# 2_power.net
KiCad netlist of a schematic drawn in Altium Designer
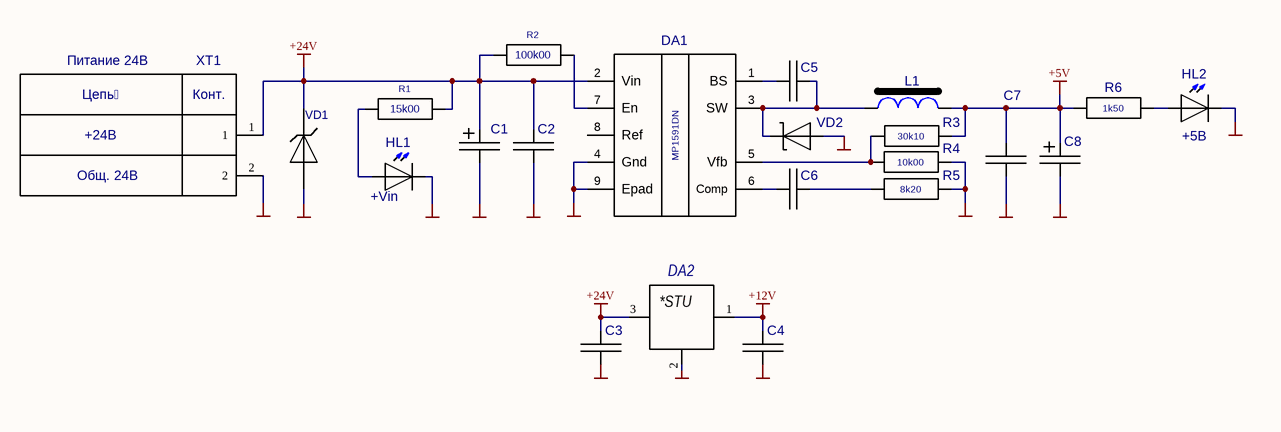
[diagram p0: 2 power.SchDoc]

(export (version "E")
  (design (tool "Eeschema 10.0.6"))
  (components
    (comp (ref "C1")
      (value "22.0x35V")
      (footprint "конденсаторы:TC7343-D")
      (description "TC6032-D")
      (libsource (lib "*") (part "TC6032-D"))
    )
    (comp (ref "C2") (value "C0603") (footprint "конденсаторы:0603_CAP") (libsource (lib "*") (part "C0603")))
    (comp (ref "C3") (value "C0603") (footprint "конденсаторы:0603_CAP") (libsource (lib "*") (part "C0603")))
    (comp (ref "C4") (value "C0603") (footprint "конденсаторы:0603_CAP") (libsource (lib "*") (part "C0603")))
    (comp (ref "C5") (value "C0603") (footprint "конденсаторы:0603_CAP") (libsource (lib "*") (part "C0603")))
    (comp (ref "C6") (value "C0603") (footprint "конденсаторы:0603_CAP") (libsource (lib "*") (part "C0603")))
    (comp (ref "C7") (value "C0603") (footprint "конденсаторы:0603_CAP") (libsource (lib "*") (part "C0603")))
    (comp (ref "C8")
      (value "100.0x16V")
      (footprint "конденсаторы:TC7343-D")
      (description "TC7343-D")
      (libsource (lib "конденсаторы") (part "TC7343-D"))
    )
    (comp (ref "DA1") (value "MP1591DN") (footprint "HSOP8") (libsource (lib "*") (part "MP1591DN")))
    (comp (ref "DA2")
      (value "L78L12ABUTR")
      (footprint "SOT-89")
      (fields (field (name "PUBLISHER") "Andrew Danich"))
      (libsource (lib "Lib_IMP_GOST") (part "L78L-Series"))
    )
    (comp (ref "HL1")
      (value "KP-2012SYC")
      (footprint "индикаторные эл-ты:KP-2012_YEL")
      (libsource (lib "*") (part "KP-2012"))
    )
    (comp (ref "HL2")
      (value "KP-2012MGC")
      (footprint "индикаторные эл-ты:KP-2012_GRN")
      (libsource (lib "*") (part "KP-2012"))
    )
    (comp (ref "L1")
      (value "22µH CDRH124NP-220MC")
      (footprint "CDRH124")
      (description "CDRH124")
      (libsource (lib "*") (part "CDRH124"))
    )
    (comp (ref "R1")
      (value "15k00")
      (footprint "резисторы:0603_RES")
      (description "R0603")
      (libsource (lib "резисторы") (part "R0603"))
    )
    (comp (ref "R2")
      (value "100k00")
      (footprint "резисторы:0603_RES")
      (description "R0603")
      (libsource (lib "резисторы") (part "R0603"))
    )
    (comp (ref "R3")
      (value "30k10")
      (footprint "резисторы:0603_RES")
      (description "R0603")
      (libsource (lib "*") (part "R0603"))
    )
    (comp (ref "R4")
      (value "10k00")
      (footprint "резисторы:0603_RES")
      (description "R0603")
      (libsource (lib "*") (part "R0603"))
    )
    (comp (ref "R5")
      (value "8k20")
      (footprint "резисторы:0603_RES")
      (description "R0603")
      (libsource (lib "*") (part "R0603"))
    )
    (comp (ref "R6")
      (value "1k50")
      (footprint "резисторы:0603_RES")
      (description "R0603")
      (libsource (lib "*") (part "R0603"))
    )
    (comp (ref "VD1")
      (value "P1.5KE24A")
      (footprint "диоды:DO-201AD")
      (libsource (lib "диоды") (part "P1.5KE_X_(A)"))
    )
    (comp (ref "VD2")
      (value "STPS3L60U")
      (footprint "SMB-STPS3L60U")
      (libsource (lib "*") (part "STPS3L60U"))
    )
    (comp (ref "XT1")
      (value "XY301VA-5.0-2P-12")
      (footprint "разъёмы:301-021-12")
      (description "Клеммник винтовой, 2-контактный, 5мм, прямой")
      (libsource (lib "разъёмы") (part "301-021-12"))
    )
  )
  (nets
    (net (code "1") (name "+5V") (class "Default")
      (node (ref "C7") (pin "1") (pinfunction "1_1") (pintype "passive"))
      (node (ref "C8") (pin "1") (pinfunction "1_1") (pintype "passive"))
      (node (ref "L1") (pin "2") (pinfunction "2_2") (pintype "passive"))
      (node (ref "R3") (pin "2") (pinfunction "2_2") (pintype "passive"))
      (node (ref "R6") (pin "1") (pinfunction "1_1") (pintype "passive"))
    )
    (net (code "2") (name "+12V") (class "Default")
      (node (ref "C4") (pin "1") (pinfunction "1_1") (pintype "passive"))
      (node (ref "DA2") (pin "1") (pinfunction "Out_1") (pintype "power_in"))
    )
    (net (code "3") (name "+24V") (class "Default")
      (node (ref "C1") (pin "1") (pinfunction "1_1") (pintype "passive"))
      (node (ref "C2") (pin "1") (pinfunction "1_1") (pintype "passive"))
      (node (ref "C3") (pin "1") (pinfunction "1_1") (pintype "passive"))
      (node (ref "DA1") (pin "2") (pinfunction "Vin_2") (pintype "passive"))
      (node (ref "DA2") (pin "3") (pinfunction "In_3") (pintype "power_in"))
      (node (ref "R1") (pin "2") (pinfunction "2_2") (pintype "passive"))
      (node (ref "R2") (pin "1") (pinfunction "1_1") (pintype "passive"))
      (node (ref "VD1") (pin "2") (pinfunction "C_2") (pintype "passive"))
      (node (ref "XT1") (pin "1") (pinfunction "1_1") (pintype "passive"))
    )
    (net (code "4") (name "GND") (class "Default")
      (node (ref "C1") (pin "2") (pinfunction "2_2") (pintype "passive"))
      (node (ref "C2") (pin "2") (pinfunction "2_2") (pintype "passive"))
      (node (ref "C3") (pin "2") (pinfunction "2_2") (pintype "passive"))
      (node (ref "C4") (pin "2") (pinfunction "2_2") (pintype "passive"))
      (node (ref "C7") (pin "2") (pinfunction "2_2") (pintype "passive"))
      (node (ref "C8") (pin "2") (pinfunction "2_2") (pintype "passive"))
      (node (ref "DA1") (pin "4") (pinfunction "Gnd_4") (pintype "passive"))
      (node (ref "DA1") (pin "9") (pinfunction "Epad_9") (pintype "passive"))
      (node (ref "DA2") (pin "2") (pinfunction "GND_2") (pintype "power_in"))
      (node (ref "HL1") (pin "2") (pinfunction "K_2") (pintype "passive"))
      (node (ref "HL2") (pin "2") (pinfunction "K_2") (pintype "passive"))
      (node (ref "R4") (pin "2") (pinfunction "2_2") (pintype "passive"))
      (node (ref "R5") (pin "2") (pinfunction "2_2") (pintype "passive"))
      (node (ref "VD1") (pin "1") (pinfunction "A_1") (pintype "passive"))
      (node (ref "VD2") (pin "1") (pinfunction "A_1") (pintype "passive"))
      (node (ref "XT1") (pin "2") (pinfunction "2_2") (pintype "passive"))
    )
    (net (code "5") (name "Net-(C6-Pad2)") (class "Default")
      (node (ref "C6") (pin "2") (pinfunction "2_2") (pintype "passive"))
      (node (ref "R5") (pin "1") (pinfunction "1_1") (pintype "passive"))
    )
    (net (code "6") (name "Net-(DA1-BS)") (class "Default")
      (node (ref "C5") (pin "1") (pinfunction "1_1") (pintype "passive"))
      (node (ref "DA1") (pin "1") (pinfunction "BS_1") (pintype "passive"))
    )
    (net (code "7") (name "Net-(DA1-Comp)") (class "Default")
      (node (ref "C6") (pin "1") (pinfunction "1_1") (pintype "passive"))
      (node (ref "DA1") (pin "6") (pinfunction "Comp_6") (pintype "passive"))
    )
    (net (code "8") (name "Net-(DA1-En)") (class "Default")
      (node (ref "DA1") (pin "7") (pinfunction "En_7") (pintype "passive"))
      (node (ref "R2") (pin "2") (pinfunction "2_2") (pintype "passive"))
    )
    (net (code "9") (name "Net-(DA1-SW)") (class "Default")
      (node (ref "C5") (pin "2") (pinfunction "2_2") (pintype "passive"))
      (node (ref "DA1") (pin "3") (pinfunction "SW_3") (pintype "passive"))
      (node (ref "L1") (pin "1") (pinfunction "1_1") (pintype "passive"))
      (node (ref "VD2") (pin "2") (pinfunction "K_2") (pintype "passive"))
    )
    (net (code "10") (name "Net-(DA1-Vfb)") (class "Default")
      (node (ref "DA1") (pin "5") (pinfunction "Vfb_5") (pintype "passive"))
      (node (ref "R3") (pin "1") (pinfunction "1_1") (pintype "passive"))
      (node (ref "R4") (pin "1") (pinfunction "1_1") (pintype "passive"))
    )
    (net (code "11") (name "Net-(HL1-A)") (class "Default")
      (node (ref "HL1") (pin "1") (pinfunction "A_1") (pintype "passive"))
      (node (ref "R1") (pin "1") (pinfunction "1_1") (pintype "passive"))
    )
    (net (code "12") (name "Net-(HL2-A)") (class "Default")
      (node (ref "HL2") (pin "1") (pinfunction "A_1") (pintype "passive"))
      (node (ref "R6") (pin "2") (pinfunction "2_2") (pintype "passive"))
    )
    (net (code "13") (name "unconnected-(DA1-Ref-Pad8)") (class "Default")
      (node (ref "DA1") (pin "8") (pinfunction "Ref_8") (pintype "passive"))
    )
  )
)
